# Corona_Box_Circuit.net
KiCad netlist of a schematic drawn in EasyEDA
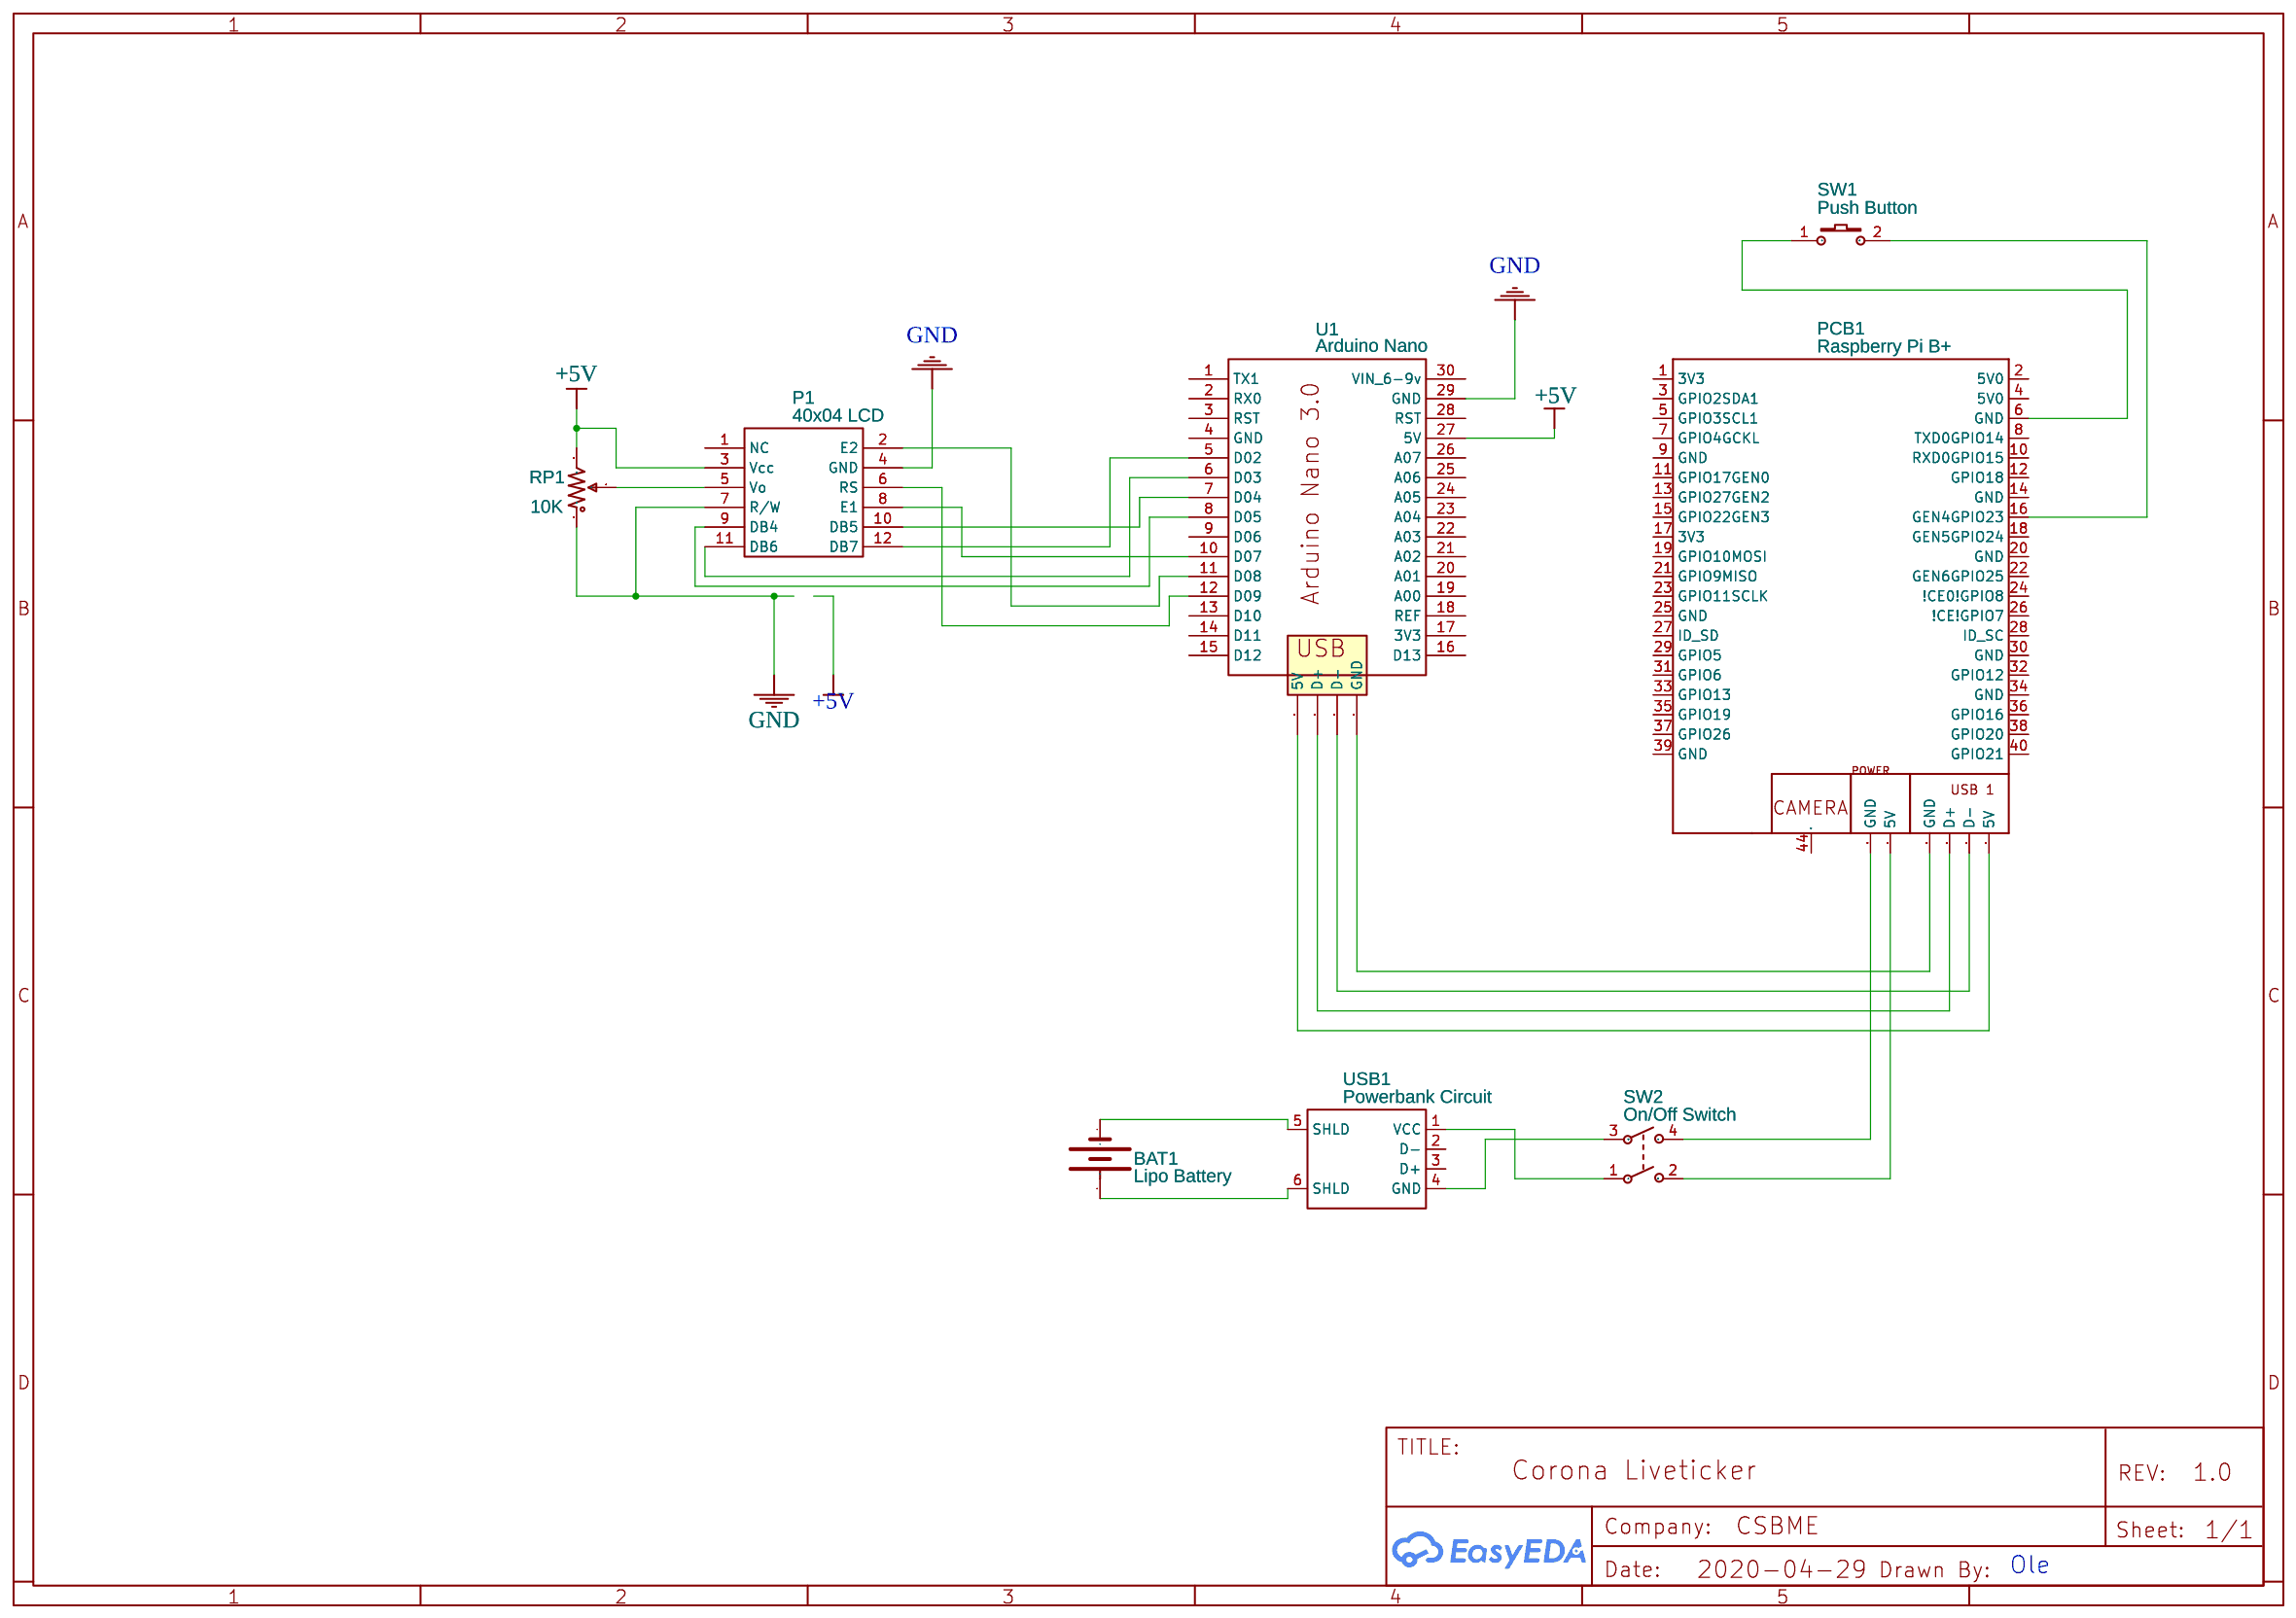
[diagram p0: schematic sheet]

(export (version "E")
  (design (tool "Eeschema 10.0.6"))
  (components
    (comp (ref "BAT1") (value "Lipo Battery") (libsource (lib "") (part "BATTERY")))
    (comp (ref "DS") (value "none") (libsource (lib "") (part "Unknown_665_-460")))
    (comp (ref "P1") (value "40x04 LCD") (libsource (lib "") (part "DS1013-12R_LCD40*4")))
    (comp (ref "PCB1")
      (value "Raspberry Pi B+")
      (libsource (lib "") (part "RASPBERRY-PI-B+_RASPBERRY_PI_3_MINE"))
    )
    (comp (ref "RP1") (value "10K") (libsource (lib "") (part "R_3386P_US")))
    (comp (ref "SW1")
      (value "Push Button")
      (fields
        (field (name "BOM_Manufacturer Part") "K2-1107ST-A4SW-06")
        (field (name "BOM_Supplier Part") "C118141")
      )
      (libsource (lib "") (part "K2-3.6×6.1_SMD"))
    )
    (comp (ref "SW2") (value "On/Off Switch") (libsource (lib "") (part "SW_DPST")))
    (comp (ref "U1")
      (value "Arduino Nano")
      (fields (field (name "BOM_Manufacturer Part") "ArduinoNanov3"))
      (libsource (lib "") (part "ARDUINONANO V3"))
    )
    (comp (ref "USB1")
      (value "Powerbank Circuit")
      (fields
        (field (name "BOM_Manufacturer Part") "USB-A-F-180-W")
        (field (name "BOM_Supplier Part") "C168706")
      )
      (libsource (lib "") (part "Powerbank"))
    )
  )
  (nets
    (net (code "1") (name "+5V") (class "Default")
      (node (ref "P1") (pin "3") (pinfunction "Vcc_3") (pintype "unspecified"))
      (node (ref "RP1") (pin "3") (pinfunction "3_3") (pintype "unspecified"))
      (node (ref "U1") (pin "27") (pinfunction "5V_27") (pintype "unspecified"))
    )
    (net (code "2") (name "GND") (class "Default")
      (node (ref "P1") (pin "4") (pinfunction "GND_4") (pintype "unspecified"))
      (node (ref "P1") (pin "7") (pinfunction "R/W_7") (pintype "unspecified"))
      (node (ref "RP1") (pin "1") (pinfunction "1_1") (pintype "unspecified"))
      (node (ref "U1") (pin "29") (pinfunction "GND_29") (pintype "unspecified"))
    )
    (net (code "3") (name "Net-(BAT1-Pad+)") (class "Default")
      (node (ref "BAT1") (pin "+") (pinfunction "+_+") (pintype "passive"))
      (node (ref "USB1") (pin "6") (pinfunction "SHLD_6") (pintype "unspecified"))
    )
    (net (code "4") (name "Net-(BAT1-Pad-)") (class "Default")
      (node (ref "BAT1") (pin "-") (pinfunction "-_-") (pintype "passive"))
      (node (ref "USB1") (pin "5") (pinfunction "SHLD_5") (pintype "unspecified"))
    )
    (net (code "5") (name "Net-(DS-D+)") (class "Default")
      (node (ref "DS") (pin "5V") (pinfunction "D+_5V") (pintype "unspecified"))
      (node (ref "PCB1") (pin "PE_BR") (pinfunction "D+_PE_BR") (pintype "unspecified"))
    )
    (net (code "6") (name "Net-(DS-D-)") (class "Default")
      (node (ref "DS") (pin "5V") (pinfunction "D-_5V") (pintype "unspecified"))
      (node (ref "PCB1") (pin "PE_BR") (pinfunction "D-_PE_BR") (pintype "unspecified"))
    )
    (net (code "7") (name "Net-(DS-GND)") (class "Default")
      (node (ref "DS") (pin "5V") (pinfunction "GND_5V") (pintype "unspecified"))
      (node (ref "PCB1") (pin "PE_BR") (pinfunction "GND_PE_BR") (pintype "unspecified"))
    )
    (net (code "8") (name "Net-(DS-Pad5V)") (class "Default")
      (node (ref "DS") (pin "5V") (pinfunction "5V_5V") (pintype "unspecified"))
      (node (ref "PCB1") (pin "PE_BR") (pinfunction "5V_PE_BR") (pintype "unspecified"))
    )
    (net (code "9") (name "Net-(P1-DB4)") (class "Default")
      (node (ref "P1") (pin "9") (pinfunction "DB4_9") (pintype "unspecified"))
      (node (ref "U1") (pin "8") (pinfunction "D05_8") (pintype "unspecified"))
    )
    (net (code "10") (name "Net-(P1-DB5)") (class "Default")
      (node (ref "P1") (pin "10") (pinfunction "DB5_10") (pintype "unspecified"))
      (node (ref "U1") (pin "7") (pinfunction "D04_7") (pintype "unspecified"))
    )
    (net (code "11") (name "Net-(P1-DB6)") (class "Default")
      (node (ref "P1") (pin "11") (pinfunction "DB6_11") (pintype "unspecified"))
      (node (ref "U1") (pin "6") (pinfunction "D03_6") (pintype "unspecified"))
    )
    (net (code "12") (name "Net-(P1-DB7)") (class "Default")
      (node (ref "P1") (pin "12") (pinfunction "DB7_12") (pintype "unspecified"))
      (node (ref "U1") (pin "5") (pinfunction "D02_5") (pintype "unspecified"))
    )
    (net (code "13") (name "Net-(P1-E1)") (class "Default")
      (node (ref "P1") (pin "8") (pinfunction "E1_8") (pintype "unspecified"))
      (node (ref "U1") (pin "10") (pinfunction "D07_10") (pintype "unspecified"))
    )
    (net (code "14") (name "Net-(P1-E2)") (class "Default")
      (node (ref "P1") (pin "2") (pinfunction "E2_2") (pintype "unspecified"))
      (node (ref "U1") (pin "11") (pinfunction "D08_11") (pintype "unspecified"))
    )
    (net (code "15") (name "Net-(P1-RS)") (class "Default")
      (node (ref "P1") (pin "6") (pinfunction "RS_6") (pintype "unspecified"))
      (node (ref "U1") (pin "12") (pinfunction "D09_12") (pintype "unspecified"))
    )
    (net (code "16") (name "Net-(P1-Vo)") (class "Default")
      (node (ref "P1") (pin "5") (pinfunction "Vo_5") (pintype "unspecified"))
      (node (ref "RP1") (pin "2") (pinfunction "2_2") (pintype "unspecified"))
    )
    (net (code "17") (name "Net-(PCB1-5V-Pad42)") (class "Default")
      (node (ref "PCB1") (pin "42") (pinfunction "5V_42") (pintype "unspecified"))
      (node (ref "SW2") (pin "2") (pinfunction "2_2") (pintype "input"))
    )
    (net (code "18") (name "Net-(PCB1-GEN4GPIO23)") (class "Default")
      (node (ref "PCB1") (pin "16") (pinfunction "GEN4GPIO23_16") (pintype "unspecified"))
      (node (ref "SW1") (pin "2") (pinfunction "2_2") (pintype "unspecified"))
    )
    (net (code "19") (name "Net-(PCB1-GND-Pad6)") (class "Default")
      (node (ref "PCB1") (pin "6") (pinfunction "GND_6") (pintype "unspecified"))
      (node (ref "SW1") (pin "1") (pinfunction "1_1") (pintype "unspecified"))
    )
    (net (code "20") (name "Net-(PCB1-GND-Pad43)") (class "Default")
      (node (ref "PCB1") (pin "43") (pinfunction "GND_43") (pintype "unspecified"))
      (node (ref "SW2") (pin "4") (pinfunction "4_4") (pintype "input"))
    )
    (net (code "21") (name "Net-(USB1-GND)") (class "Default")
      (node (ref "SW2") (pin "3") (pinfunction "3_3") (pintype "input"))
      (node (ref "USB1") (pin "4") (pinfunction "GND_4") (pintype "input"))
    )
    (net (code "22") (name "Net-(USB1-VCC)") (class "Default")
      (node (ref "SW2") (pin "1") (pinfunction "1_1") (pintype "input"))
      (node (ref "USB1") (pin "1") (pinfunction "VCC_1") (pintype "input"))
    )
    (net (code "23") (name "unconnected-(P1-NC-Pad1)") (class "Default")
      (node (ref "P1") (pin "1") (pinfunction "NC_1") (pintype "unspecified"))
    )
    (net (code "24") (name "unconnected-(PCB1-!CE!GPIO7-Pad26)") (class "Default")
      (node (ref "PCB1") (pin "26") (pinfunction "!CE!GPIO7_26") (pintype "unspecified"))
    )
    (net (code "25") (name "unconnected-(PCB1-!CE0!GPIO8-Pad24)") (class "Default")
      (node (ref "PCB1") (pin "24") (pinfunction "!CE0!GPIO8_24") (pintype "unspecified"))
    )
    (net (code "26") (name "unconnected-(PCB1-3V3-Pad1)") (class "Default")
      (node (ref "PCB1") (pin "1") (pinfunction "3V3_1") (pintype "unspecified"))
    )
    (net (code "27") (name "unconnected-(PCB1-3V3-Pad17)") (class "Default")
      (node (ref "PCB1") (pin "17") (pinfunction "3V3_17") (pintype "unspecified"))
    )
    (net (code "28") (name "unconnected-(PCB1-5V0-Pad2)") (class "Default")
      (node (ref "PCB1") (pin "2") (pinfunction "5V0_2") (pintype "unspecified"))
    )
    (net (code "29") (name "unconnected-(PCB1-5V0-Pad4)") (class "Default")
      (node (ref "PCB1") (pin "4") (pinfunction "5V0_4") (pintype "unspecified"))
    )
    (net (code "30") (name "unconnected-(PCB1-27-Pad44)") (class "Default")
      (node (ref "PCB1") (pin "44") (pinfunction "27_44") (pintype "unspecified"))
    )
    (net (code "31") (name "unconnected-(PCB1-GEN5GPIO24-Pad18)") (class "Default")
      (node (ref "PCB1") (pin "18") (pinfunction "GEN5GPIO24_18") (pintype "unspecified"))
    )
    (net (code "32") (name "unconnected-(PCB1-GEN6GPIO25-Pad22)") (class "Default")
      (node (ref "PCB1") (pin "22") (pinfunction "GEN6GPIO25_22") (pintype "unspecified"))
    )
    (net (code "33") (name "unconnected-(PCB1-GND-Pad9)") (class "Default")
      (node (ref "PCB1") (pin "9") (pinfunction "GND_9") (pintype "unspecified"))
    )
    (net (code "34") (name "unconnected-(PCB1-GND-Pad14)") (class "Default")
      (node (ref "PCB1") (pin "14") (pinfunction "GND_14") (pintype "unspecified"))
    )
    (net (code "35") (name "unconnected-(PCB1-GND-Pad20)") (class "Default")
      (node (ref "PCB1") (pin "20") (pinfunction "GND_20") (pintype "unspecified"))
    )
    (net (code "36") (name "unconnected-(PCB1-GND-Pad25)") (class "Default")
      (node (ref "PCB1") (pin "25") (pinfunction "GND_25") (pintype "unspecified"))
    )
    (net (code "37") (name "unconnected-(PCB1-GND-Pad30)") (class "Default")
      (node (ref "PCB1") (pin "30") (pinfunction "GND_30") (pintype "unspecified"))
    )
    (net (code "38") (name "unconnected-(PCB1-GND-Pad34)") (class "Default")
      (node (ref "PCB1") (pin "34") (pinfunction "GND_34") (pintype "unspecified"))
    )
    (net (code "39") (name "unconnected-(PCB1-GND-Pad39)") (class "Default")
      (node (ref "PCB1") (pin "39") (pinfunction "GND_39") (pintype "unspecified"))
    )
    (net (code "40") (name "unconnected-(PCB1-GPIO2SDA1-Pad3)") (class "Default")
      (node (ref "PCB1") (pin "3") (pinfunction "GPIO2SDA1_3") (pintype "unspecified"))
    )
    (net (code "41") (name "unconnected-(PCB1-GPIO3SCL1-Pad5)") (class "Default")
      (node (ref "PCB1") (pin "5") (pinfunction "GPIO3SCL1_5") (pintype "unspecified"))
    )
    (net (code "42") (name "unconnected-(PCB1-GPIO4GCKL-Pad7)") (class "Default")
      (node (ref "PCB1") (pin "7") (pinfunction "GPIO4GCKL_7") (pintype "unspecified"))
    )
    (net (code "43") (name "unconnected-(PCB1-GPIO5-Pad29)") (class "Default")
      (node (ref "PCB1") (pin "29") (pinfunction "GPIO5_29") (pintype "unspecified"))
    )
    (net (code "44") (name "unconnected-(PCB1-GPIO6-Pad31)") (class "Default")
      (node (ref "PCB1") (pin "31") (pinfunction "GPIO6_31") (pintype "unspecified"))
    )
    (net (code "45") (name "unconnected-(PCB1-GPIO9MISO-Pad21)") (class "Default")
      (node (ref "PCB1") (pin "21") (pinfunction "GPIO9MISO_21") (pintype "unspecified"))
    )
    (net (code "46") (name "unconnected-(PCB1-GPIO10MOSI-Pad19)") (class "Default")
      (node (ref "PCB1") (pin "19") (pinfunction "GPIO10MOSI_19") (pintype "unspecified"))
    )
    (net (code "47") (name "unconnected-(PCB1-GPIO11SCLK-Pad23)") (class "Default")
      (node (ref "PCB1") (pin "23") (pinfunction "GPIO11SCLK_23") (pintype "unspecified"))
    )
    (net (code "48") (name "unconnected-(PCB1-GPIO12-Pad32)") (class "Default")
      (node (ref "PCB1") (pin "32") (pinfunction "GPIO12_32") (pintype "unspecified"))
    )
    (net (code "49") (name "unconnected-(PCB1-GPIO13-Pad33)") (class "Default")
      (node (ref "PCB1") (pin "33") (pinfunction "GPIO13_33") (pintype "unspecified"))
    )
    (net (code "50") (name "unconnected-(PCB1-GPIO16-Pad36)") (class "Default")
      (node (ref "PCB1") (pin "36") (pinfunction "GPIO16_36") (pintype "unspecified"))
    )
    (net (code "51") (name "unconnected-(PCB1-GPIO17GEN0-Pad11)") (class "Default")
      (node (ref "PCB1") (pin "11") (pinfunction "GPIO17GEN0_11") (pintype "unspecified"))
    )
    (net (code "52") (name "unconnected-(PCB1-GPIO18-Pad12)") (class "Default")
      (node (ref "PCB1") (pin "12") (pinfunction "GPIO18_12") (pintype "unspecified"))
    )
    (net (code "53") (name "unconnected-(PCB1-GPIO19-Pad35)") (class "Default")
      (node (ref "PCB1") (pin "35") (pinfunction "GPIO19_35") (pintype "unspecified"))
    )
    (net (code "54") (name "unconnected-(PCB1-GPIO20-Pad38)") (class "Default")
      (node (ref "PCB1") (pin "38") (pinfunction "GPIO20_38") (pintype "unspecified"))
    )
    (net (code "55") (name "unconnected-(PCB1-GPIO21-Pad40)") (class "Default")
      (node (ref "PCB1") (pin "40") (pinfunction "GPIO21_40") (pintype "unspecified"))
    )
    (net (code "56") (name "unconnected-(PCB1-GPIO22GEN3-Pad15)") (class "Default")
      (node (ref "PCB1") (pin "15") (pinfunction "GPIO22GEN3_15") (pintype "unspecified"))
    )
    (net (code "57") (name "unconnected-(PCB1-GPIO26-Pad37)") (class "Default")
      (node (ref "PCB1") (pin "37") (pinfunction "GPIO26_37") (pintype "unspecified"))
    )
    (net (code "58") (name "unconnected-(PCB1-GPIO27GEN2-Pad13)") (class "Default")
      (node (ref "PCB1") (pin "13") (pinfunction "GPIO27GEN2_13") (pintype "unspecified"))
    )
    (net (code "59") (name "unconnected-(PCB1-ID_SC-Pad28)") (class "Default")
      (node (ref "PCB1") (pin "28") (pinfunction "ID_SC_28") (pintype "unspecified"))
    )
    (net (code "60") (name "unconnected-(PCB1-ID_SD-Pad27)") (class "Default")
      (node (ref "PCB1") (pin "27") (pinfunction "ID_SD_27") (pintype "unspecified"))
    )
    (net (code "61") (name "unconnected-(PCB1-RXD0GPIO15-Pad10)") (class "Default")
      (node (ref "PCB1") (pin "10") (pinfunction "RXD0GPIO15_10") (pintype "unspecified"))
    )
    (net (code "62") (name "unconnected-(PCB1-TXD0GPIO14-Pad8)") (class "Default")
      (node (ref "PCB1") (pin "8") (pinfunction "TXD0GPIO14_8") (pintype "unspecified"))
    )
    (net (code "63") (name "unconnected-(U1-3V3-Pad17)") (class "Default")
      (node (ref "U1") (pin "17") (pinfunction "3V3_17") (pintype "unspecified"))
    )
    (net (code "64") (name "unconnected-(U1-A00-Pad19)") (class "Default")
      (node (ref "U1") (pin "19") (pinfunction "A00_19") (pintype "unspecified"))
    )
    (net (code "65") (name "unconnected-(U1-A01-Pad20)") (class "Default")
      (node (ref "U1") (pin "20") (pinfunction "A01_20") (pintype "unspecified"))
    )
    (net (code "66") (name "unconnected-(U1-A02-Pad21)") (class "Default")
      (node (ref "U1") (pin "21") (pinfunction "A02_21") (pintype "unspecified"))
    )
    (net (code "67") (name "unconnected-(U1-A03-Pad22)") (class "Default")
      (node (ref "U1") (pin "22") (pinfunction "A03_22") (pintype "unspecified"))
    )
    (net (code "68") (name "unconnected-(U1-A04-Pad23)") (class "Default")
      (node (ref "U1") (pin "23") (pinfunction "A04_23") (pintype "unspecified"))
    )
    (net (code "69") (name "unconnected-(U1-A05-Pad24)") (class "Default")
      (node (ref "U1") (pin "24") (pinfunction "A05_24") (pintype "unspecified"))
    )
    (net (code "70") (name "unconnected-(U1-A06-Pad25)") (class "Default")
      (node (ref "U1") (pin "25") (pinfunction "A06_25") (pintype "unspecified"))
    )
    (net (code "71") (name "unconnected-(U1-A07-Pad26)") (class "Default")
      (node (ref "U1") (pin "26") (pinfunction "A07_26") (pintype "unspecified"))
    )
    (net (code "72") (name "unconnected-(U1-D06-Pad9)") (class "Default")
      (node (ref "U1") (pin "9") (pinfunction "D06_9") (pintype "unspecified"))
    )
    (net (code "73") (name "unconnected-(U1-D10-Pad13)") (class "Default")
      (node (ref "U1") (pin "13") (pinfunction "D10_13") (pintype "unspecified"))
    )
    (net (code "74") (name "unconnected-(U1-D11-Pad14)") (class "Default")
      (node (ref "U1") (pin "14") (pinfunction "D11_14") (pintype "unspecified"))
    )
    (net (code "75") (name "unconnected-(U1-D12-Pad15)") (class "Default")
      (node (ref "U1") (pin "15") (pinfunction "D12_15") (pintype "unspecified"))
    )
    (net (code "76") (name "unconnected-(U1-D13-Pad16)") (class "Default")
      (node (ref "U1") (pin "16") (pinfunction "D13_16") (pintype "unspecified"))
    )
    (net (code "77") (name "unconnected-(U1-GND-Pad4)") (class "Default")
      (node (ref "U1") (pin "4") (pinfunction "GND_4") (pintype "unspecified"))
    )
    (net (code "78") (name "unconnected-(U1-REF-Pad18)") (class "Default")
      (node (ref "U1") (pin "18") (pinfunction "REF_18") (pintype "unspecified"))
    )
    (net (code "79") (name "unconnected-(U1-RST-Pad3)") (class "Default")
      (node (ref "U1") (pin "3") (pinfunction "RST_3") (pintype "unspecified"))
    )
    (net (code "80") (name "unconnected-(U1-RST-Pad28)") (class "Default")
      (node (ref "U1") (pin "28") (pinfunction "RST_28") (pintype "unspecified"))
    )
    (net (code "81") (name "unconnected-(U1-RX0-Pad2)") (class "Default")
      (node (ref "U1") (pin "2") (pinfunction "RX0_2") (pintype "unspecified"))
    )
    (net (code "82") (name "unconnected-(U1-TX1-Pad1)") (class "Default")
      (node (ref "U1") (pin "1") (pinfunction "TX1_1") (pintype "unspecified"))
    )
    (net (code "83") (name "unconnected-(U1-VIN_6-9v-Pad30)") (class "Default")
      (node (ref "U1") (pin "30") (pinfunction "VIN_6-9v_30") (pintype "unspecified"))
    )
    (net (code "84") (name "unconnected-(USB1-D+-Pad3)") (class "Default")
      (node (ref "USB1") (pin "3") (pinfunction "D+_3") (pintype "input"))
    )
    (net (code "85") (name "unconnected-(USB1-D--Pad2)") (class "Default")
      (node (ref "USB1") (pin "2") (pinfunction "D-_2") (pintype "input"))
    )
  )
)
